# ArmBoardNew-New_Main_Board.net
KiCad netlist of a schematic drawn in EAGLE
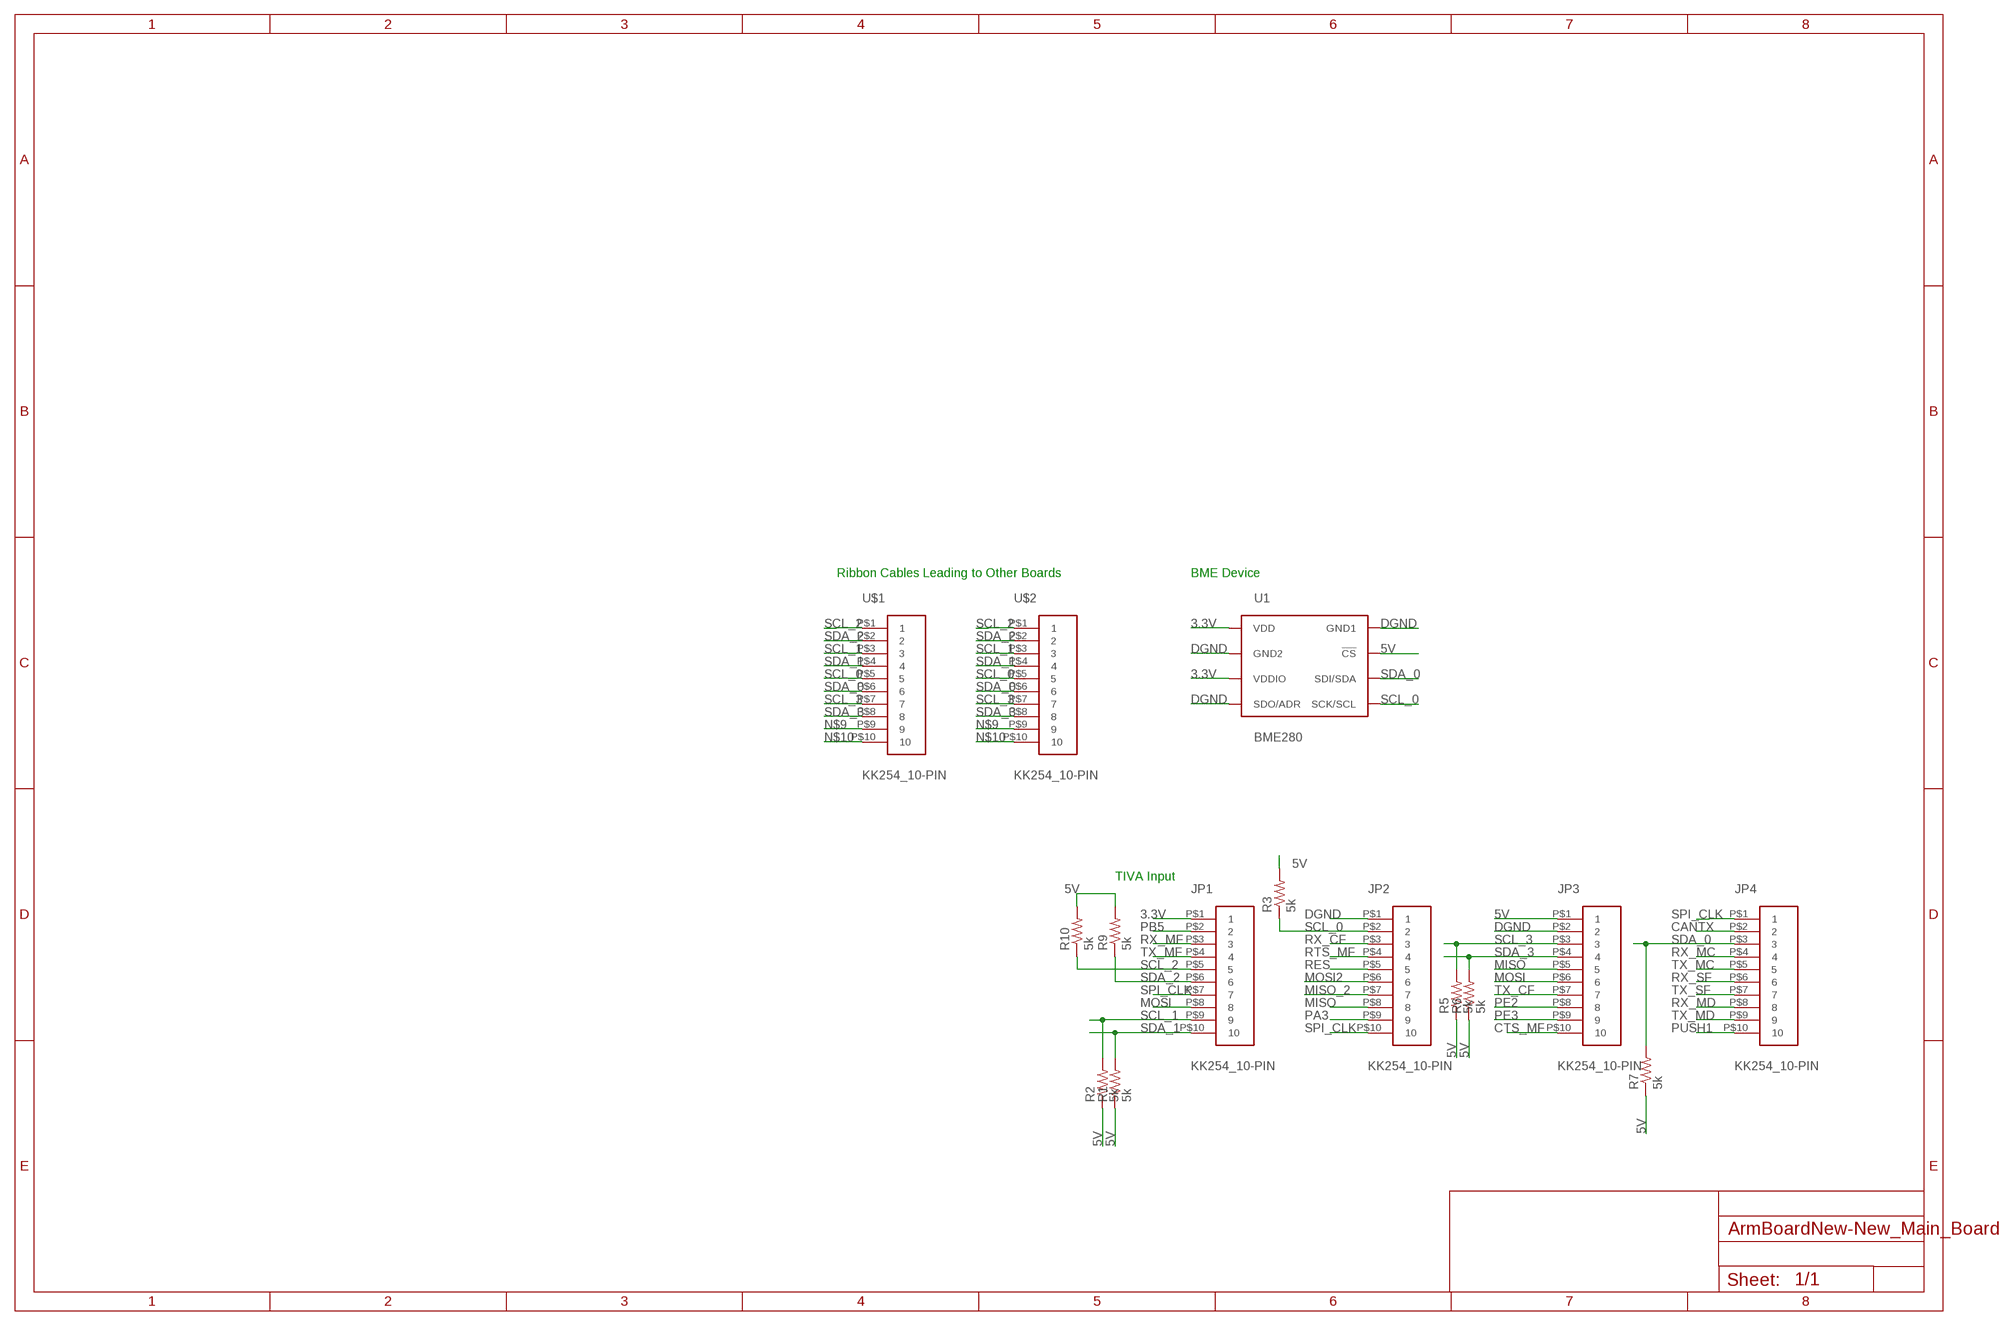
[diagram p0: schematic, sheet 1]

(export (version "E")
  (design (tool "Eeschema 10.0.6"))
  (components
    (comp (ref "JP1")
      (value "KK254_10-PIN")
      (footprint "eagle-import:KK254_10-PIN")
      (libsource (lib "eagle-import") (part "KK254_10-PIN"))
    )
    (comp (ref "JP2")
      (value "KK254_10-PIN")
      (footprint "eagle-import:KK254_10-PIN")
      (libsource (lib "eagle-import") (part "KK254_10-PIN"))
    )
    (comp (ref "JP3")
      (value "KK254_10-PIN")
      (footprint "eagle-import:KK254_10-PIN")
      (libsource (lib "eagle-import") (part "KK254_10-PIN"))
    )
    (comp (ref "JP4")
      (value "KK254_10-PIN")
      (footprint "eagle-import:KK254_10-PIN")
      (libsource (lib "eagle-import") (part "KK254_10-PIN"))
    )
    (comp (ref "R1")
      (value "5k")
      (footprint "eagle-import:R0805")
      (libsource (lib "eagle-import") (part "R-US_R0805"))
    )
    (comp (ref "R2")
      (value "5k")
      (footprint "eagle-import:R0805")
      (libsource (lib "eagle-import") (part "R-US_R0805"))
    )
    (comp (ref "R3")
      (value "5k")
      (footprint "eagle-import:R0805")
      (libsource (lib "eagle-import") (part "R-US_R0805"))
    )
    (comp (ref "R5")
      (value "5k")
      (footprint "eagle-import:R0805")
      (libsource (lib "eagle-import") (part "R-US_R0805"))
    )
    (comp (ref "R6")
      (value "5k")
      (footprint "eagle-import:R0805")
      (libsource (lib "eagle-import") (part "R-US_R0805"))
    )
    (comp (ref "R7")
      (value "5k")
      (footprint "eagle-import:R0805")
      (libsource (lib "eagle-import") (part "R-US_R0805"))
    )
    (comp (ref "R9")
      (value "5k")
      (footprint "eagle-import:R0805")
      (libsource (lib "eagle-import") (part "R-US_R0805"))
    )
    (comp (ref "R10")
      (value "5k")
      (footprint "eagle-import:R0805")
      (libsource (lib "eagle-import") (part "R-US_R0805"))
    )
    (comp (ref "U$1")
      (value "KK254_10-PIN")
      (footprint "eagle-import:KK254_10-PIN")
      (libsource (lib "eagle-import") (part "KK254_10-PIN"))
    )
    (comp (ref "U$2")
      (value "KK254_10-PIN")
      (footprint "eagle-import:KK254_10-PIN")
      (libsource (lib "eagle-import") (part "KK254_10-PIN"))
    )
    (comp (ref "U1")
      (value "BME280")
      (footprint "eagle-import:BME280_LGA")
      (libsource (lib "eagle-import") (part "BME280"))
    )
  )
  (nets
    (net (code "1") (name "/3.3V") (class "Default")
      (node (ref "JP1") (pin "P$1") (pinfunction "1_P$1") (pintype "bidirectional"))
      (node (ref "U1") (pin "P$6") (pinfunction "VDDIO_P$6") (pintype "bidirectional"))
      (node (ref "U1") (pin "P$8") (pinfunction "VDD_P$8") (pintype "bidirectional"))
    )
    (net (code "2") (name "/5V") (class "Default")
      (node (ref "JP3") (pin "P$1") (pinfunction "1_P$1") (pintype "bidirectional"))
      (node (ref "R1") (pin "1") (pinfunction "1_1") (pintype "passive"))
      (node (ref "R10") (pin "2") (pinfunction "2_2") (pintype "passive"))
      (node (ref "R2") (pin "1") (pinfunction "1_1") (pintype "passive"))
      (node (ref "R3") (pin "2") (pinfunction "2_2") (pintype "passive"))
      (node (ref "R5") (pin "1") (pinfunction "1_1") (pintype "passive"))
      (node (ref "R6") (pin "1") (pinfunction "1_1") (pintype "passive"))
      (node (ref "R7") (pin "1") (pinfunction "1_1") (pintype "passive"))
      (node (ref "R9") (pin "2") (pinfunction "2_2") (pintype "passive"))
      (node (ref "U1") (pin "P$2") (pinfunction "~{CS}_P$2") (pintype "bidirectional"))
    )
    (net (code "3") (name "/CANTX") (class "Default")
      (node (ref "JP4") (pin "P$2") (pinfunction "2_P$2") (pintype "bidirectional"))
    )
    (net (code "4") (name "/CTS_MF") (class "Default")
      (node (ref "JP3") (pin "P$10") (pinfunction "10_P$10") (pintype "bidirectional"))
    )
    (net (code "5") (name "/DGND") (class "Default")
      (node (ref "JP2") (pin "P$1") (pinfunction "1_P$1") (pintype "bidirectional"))
      (node (ref "JP3") (pin "P$2") (pinfunction "2_P$2") (pintype "bidirectional"))
      (node (ref "U1") (pin "P$1") (pinfunction "GND1_P$1") (pintype "bidirectional"))
      (node (ref "U1") (pin "P$5") (pinfunction "SDO/ADR_P$5") (pintype "bidirectional"))
      (node (ref "U1") (pin "P$7") (pinfunction "GND2_P$7") (pintype "bidirectional"))
    )
    (net (code "6") (name "/MISO") (class "Default")
      (node (ref "JP2") (pin "P$8") (pinfunction "8_P$8") (pintype "bidirectional"))
      (node (ref "JP3") (pin "P$5") (pinfunction "5_P$5") (pintype "bidirectional"))
    )
    (net (code "7") (name "/MISO_2") (class "Default")
      (node (ref "JP2") (pin "P$7") (pinfunction "7_P$7") (pintype "bidirectional"))
    )
    (net (code "8") (name "/MOSI") (class "Default")
      (node (ref "JP1") (pin "P$8") (pinfunction "8_P$8") (pintype "bidirectional"))
      (node (ref "JP3") (pin "P$6") (pinfunction "6_P$6") (pintype "bidirectional"))
    )
    (net (code "9") (name "/MOSI2") (class "Default")
      (node (ref "JP2") (pin "P$6") (pinfunction "6_P$6") (pintype "bidirectional"))
    )
    (net (code "10") (name "/N$9") (class "Default")
      (node (ref "U$1") (pin "P$9") (pinfunction "9_P$9") (pintype "bidirectional"))
      (node (ref "U$2") (pin "P$9") (pinfunction "9_P$9") (pintype "bidirectional"))
    )
    (net (code "11") (name "/N$10") (class "Default")
      (node (ref "U$1") (pin "P$10") (pinfunction "10_P$10") (pintype "bidirectional"))
      (node (ref "U$2") (pin "P$10") (pinfunction "10_P$10") (pintype "bidirectional"))
    )
    (net (code "12") (name "/PA3") (class "Default")
      (node (ref "JP2") (pin "P$9") (pinfunction "9_P$9") (pintype "bidirectional"))
    )
    (net (code "13") (name "/PB5") (class "Default")
      (node (ref "JP1") (pin "P$2") (pinfunction "2_P$2") (pintype "bidirectional"))
    )
    (net (code "14") (name "/PE2") (class "Default")
      (node (ref "JP3") (pin "P$8") (pinfunction "8_P$8") (pintype "bidirectional"))
    )
    (net (code "15") (name "/PE3") (class "Default")
      (node (ref "JP3") (pin "P$9") (pinfunction "9_P$9") (pintype "bidirectional"))
    )
    (net (code "16") (name "/PUSH1") (class "Default")
      (node (ref "JP4") (pin "P$10") (pinfunction "10_P$10") (pintype "bidirectional"))
    )
    (net (code "17") (name "/RES") (class "Default")
      (node (ref "JP2") (pin "P$5") (pinfunction "5_P$5") (pintype "bidirectional"))
    )
    (net (code "18") (name "/RTS_MF") (class "Default")
      (node (ref "JP2") (pin "P$4") (pinfunction "4_P$4") (pintype "bidirectional"))
    )
    (net (code "19") (name "/RX_CF") (class "Default")
      (node (ref "JP2") (pin "P$3") (pinfunction "3_P$3") (pintype "bidirectional"))
    )
    (net (code "20") (name "/RX_MC") (class "Default")
      (node (ref "JP4") (pin "P$4") (pinfunction "4_P$4") (pintype "bidirectional"))
    )
    (net (code "21") (name "/RX_MD") (class "Default")
      (node (ref "JP4") (pin "P$8") (pinfunction "8_P$8") (pintype "bidirectional"))
    )
    (net (code "22") (name "/RX_MF") (class "Default")
      (node (ref "JP1") (pin "P$3") (pinfunction "3_P$3") (pintype "bidirectional"))
    )
    (net (code "23") (name "/RX_SF") (class "Default")
      (node (ref "JP4") (pin "P$6") (pinfunction "6_P$6") (pintype "bidirectional"))
    )
    (net (code "24") (name "/SCL_0") (class "Default")
      (node (ref "JP2") (pin "P$2") (pinfunction "2_P$2") (pintype "bidirectional"))
      (node (ref "R3") (pin "1") (pinfunction "1_1") (pintype "passive"))
      (node (ref "U$1") (pin "P$5") (pinfunction "5_P$5") (pintype "bidirectional"))
      (node (ref "U$2") (pin "P$5") (pinfunction "5_P$5") (pintype "bidirectional"))
      (node (ref "U1") (pin "P$4") (pinfunction "SCK/SCL_P$4") (pintype "bidirectional"))
    )
    (net (code "25") (name "/SCL_1") (class "Default")
      (node (ref "JP1") (pin "P$9") (pinfunction "9_P$9") (pintype "bidirectional"))
      (node (ref "R2") (pin "2") (pinfunction "2_2") (pintype "passive"))
      (node (ref "U$1") (pin "P$3") (pinfunction "3_P$3") (pintype "bidirectional"))
      (node (ref "U$2") (pin "P$3") (pinfunction "3_P$3") (pintype "bidirectional"))
    )
    (net (code "26") (name "/SCL_2") (class "Default")
      (node (ref "JP1") (pin "P$5") (pinfunction "5_P$5") (pintype "bidirectional"))
      (node (ref "R10") (pin "1") (pinfunction "1_1") (pintype "passive"))
      (node (ref "U$1") (pin "P$1") (pinfunction "1_P$1") (pintype "bidirectional"))
      (node (ref "U$2") (pin "P$1") (pinfunction "1_P$1") (pintype "bidirectional"))
    )
    (net (code "27") (name "/SCL_3") (class "Default")
      (node (ref "JP3") (pin "P$3") (pinfunction "3_P$3") (pintype "bidirectional"))
      (node (ref "R5") (pin "2") (pinfunction "2_2") (pintype "passive"))
      (node (ref "U$1") (pin "P$7") (pinfunction "7_P$7") (pintype "bidirectional"))
      (node (ref "U$2") (pin "P$7") (pinfunction "7_P$7") (pintype "bidirectional"))
    )
    (net (code "28") (name "/SDA_0") (class "Default")
      (node (ref "JP4") (pin "P$3") (pinfunction "3_P$3") (pintype "bidirectional"))
      (node (ref "R7") (pin "2") (pinfunction "2_2") (pintype "passive"))
      (node (ref "U$1") (pin "P$6") (pinfunction "6_P$6") (pintype "bidirectional"))
      (node (ref "U$2") (pin "P$6") (pinfunction "6_P$6") (pintype "bidirectional"))
      (node (ref "U1") (pin "P$3") (pinfunction "SDI/SDA_P$3") (pintype "bidirectional"))
    )
    (net (code "29") (name "/SDA_1") (class "Default")
      (node (ref "JP1") (pin "P$10") (pinfunction "10_P$10") (pintype "bidirectional"))
      (node (ref "R1") (pin "2") (pinfunction "2_2") (pintype "passive"))
      (node (ref "U$1") (pin "P$4") (pinfunction "4_P$4") (pintype "bidirectional"))
      (node (ref "U$2") (pin "P$4") (pinfunction "4_P$4") (pintype "bidirectional"))
    )
    (net (code "30") (name "/SDA_2") (class "Default")
      (node (ref "JP1") (pin "P$6") (pinfunction "6_P$6") (pintype "bidirectional"))
      (node (ref "R9") (pin "1") (pinfunction "1_1") (pintype "passive"))
      (node (ref "U$1") (pin "P$2") (pinfunction "2_P$2") (pintype "bidirectional"))
      (node (ref "U$2") (pin "P$2") (pinfunction "2_P$2") (pintype "bidirectional"))
    )
    (net (code "31") (name "/SDA_3") (class "Default")
      (node (ref "JP3") (pin "P$4") (pinfunction "4_P$4") (pintype "bidirectional"))
      (node (ref "R6") (pin "2") (pinfunction "2_2") (pintype "passive"))
      (node (ref "U$1") (pin "P$8") (pinfunction "8_P$8") (pintype "bidirectional"))
      (node (ref "U$2") (pin "P$8") (pinfunction "8_P$8") (pintype "bidirectional"))
    )
    (net (code "32") (name "/SPI_CLK") (class "Default")
      (node (ref "JP1") (pin "P$7") (pinfunction "7_P$7") (pintype "bidirectional"))
      (node (ref "JP2") (pin "P$10") (pinfunction "10_P$10") (pintype "bidirectional"))
      (node (ref "JP4") (pin "P$1") (pinfunction "1_P$1") (pintype "bidirectional"))
    )
    (net (code "33") (name "/TX_CF") (class "Default")
      (node (ref "JP3") (pin "P$7") (pinfunction "7_P$7") (pintype "bidirectional"))
    )
    (net (code "34") (name "/TX_MC") (class "Default")
      (node (ref "JP4") (pin "P$5") (pinfunction "5_P$5") (pintype "bidirectional"))
    )
    (net (code "35") (name "/TX_MD") (class "Default")
      (node (ref "JP4") (pin "P$9") (pinfunction "9_P$9") (pintype "bidirectional"))
    )
    (net (code "36") (name "/TX_MF") (class "Default")
      (node (ref "JP1") (pin "P$4") (pinfunction "4_P$4") (pintype "bidirectional"))
    )
    (net (code "37") (name "/TX_SF") (class "Default")
      (node (ref "JP4") (pin "P$7") (pinfunction "7_P$7") (pintype "bidirectional"))
    )
  )
)
